# Poactuator_Connectors.net
KiCad netlist of a schematic drawn in Altium Designer
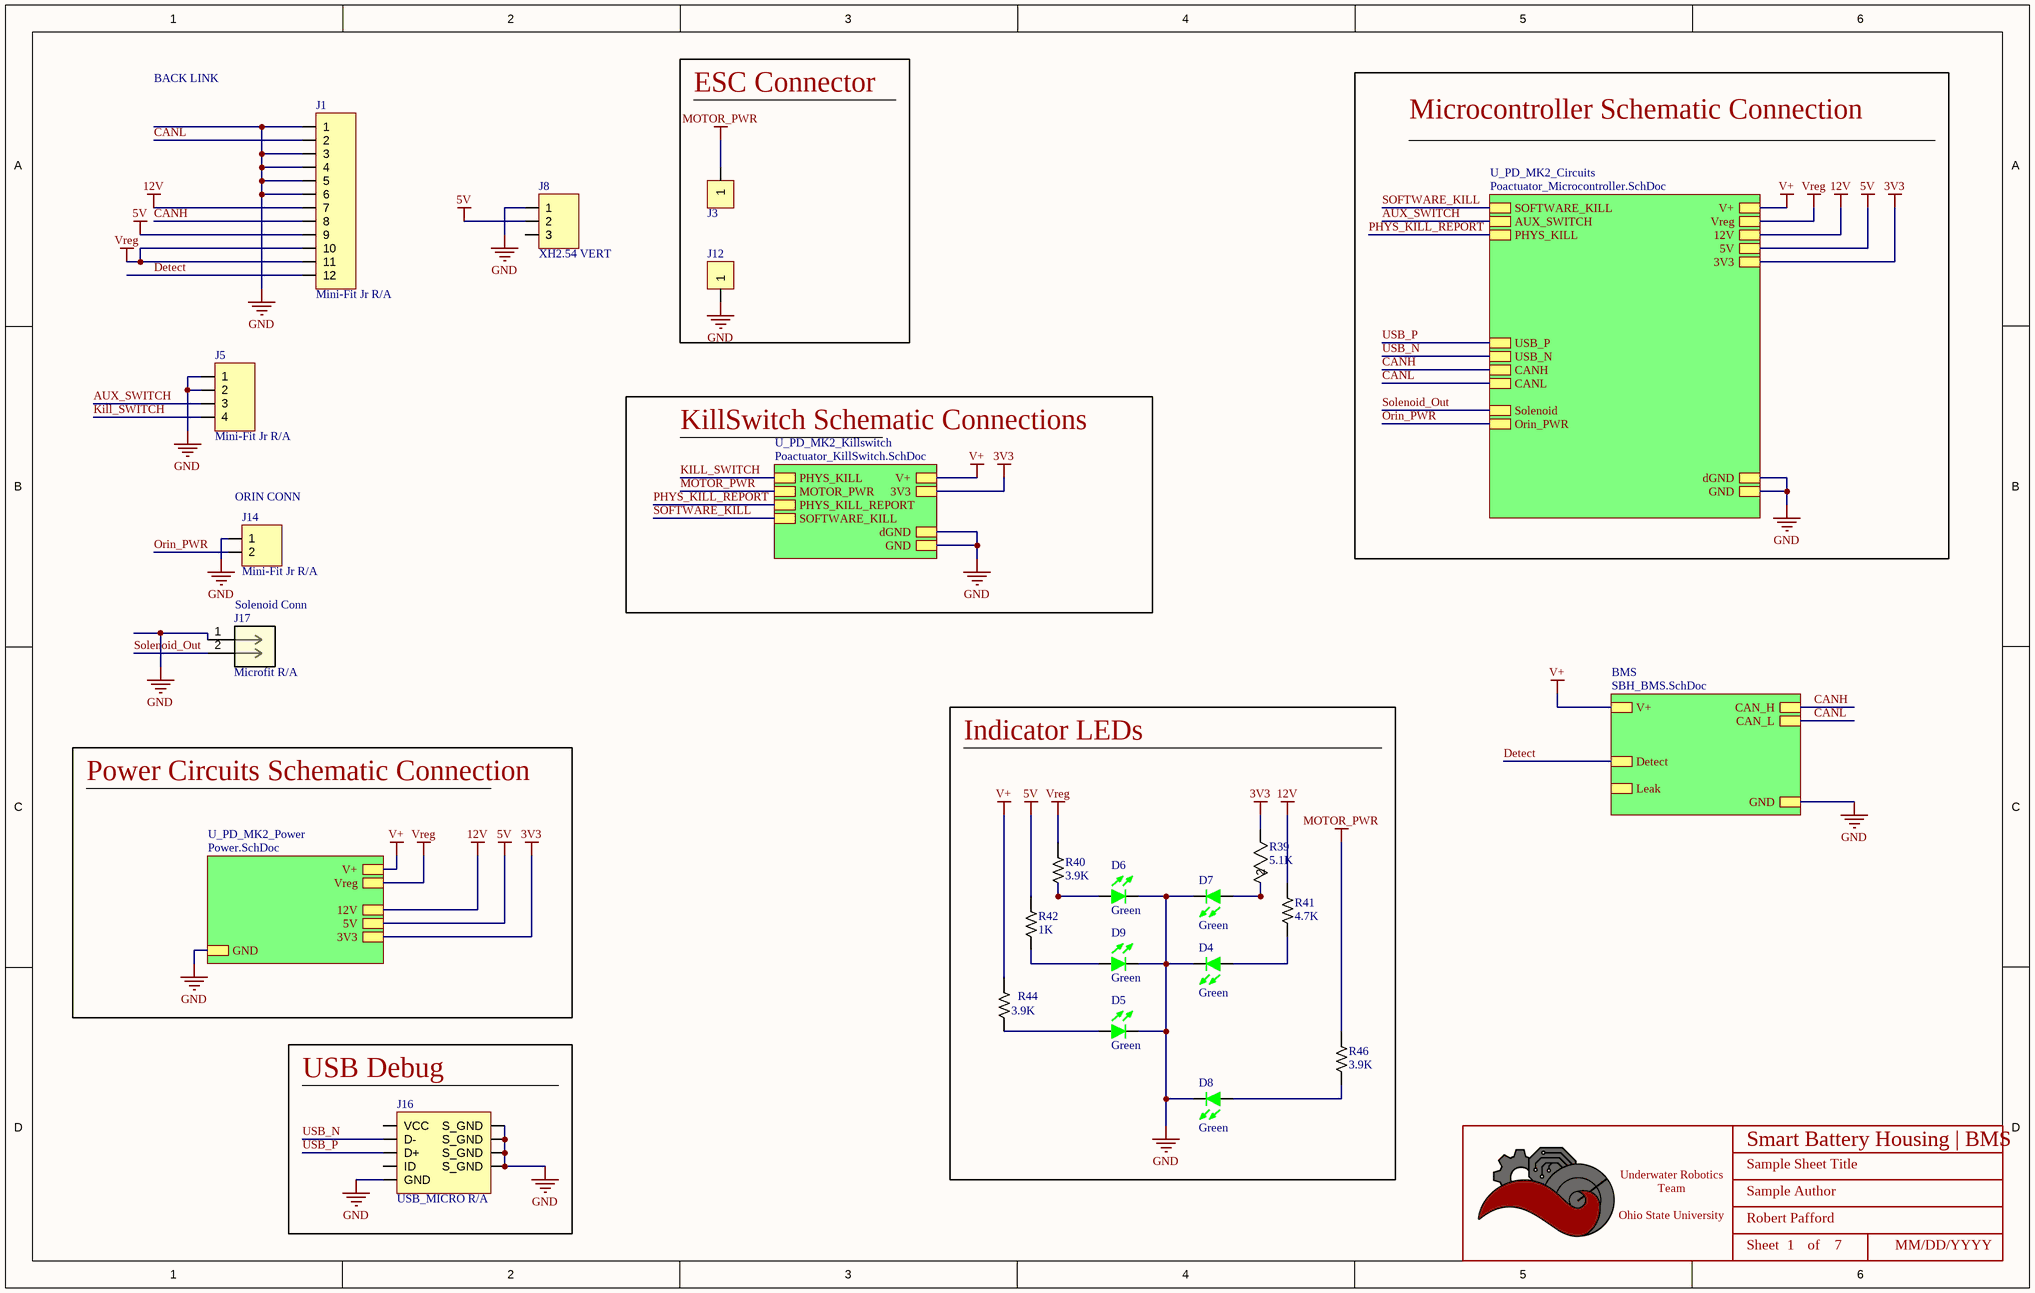
[diagram p0: Poactuator_Connectors.SchDoc]

(export (version "E")
  (design (tool "Eeschema 10.0.6"))
  (components
    (comp (ref "D4")
      (value "IN-S63AT5G")
      (footprint "LED_0603")
      (description "LED Green Vf= 3V If = 0.005A\r\nIN-S63AT5G")
      (fields (field (name "COLOR") "Green") (field (name "MADE BY") "Robert Pafford"))
      (libsource (lib "Diodes") (part "LED_Green_0603_3V"))
    )
    (comp (ref "D5")
      (value "IN-S63AT5G")
      (footprint "LED_0603")
      (description "LED Green Vf= 3V If = 0.005A\r\nIN-S63AT5G")
      (fields (field (name "COLOR") "Green") (field (name "MADE BY") "Robert Pafford"))
      (libsource (lib "Diodes") (part "LED_Green_0603_3V"))
    )
    (comp (ref "D6")
      (value "IN-S63AT5G")
      (footprint "LED_0603")
      (description "LED Green Vf= 3V If = 0.005A\r\nIN-S63AT5G")
      (fields (field (name "COLOR") "Green") (field (name "MADE BY") "Robert Pafford"))
      (libsource (lib "Diodes") (part "LED_Green_0603_3V"))
    )
    (comp (ref "D7")
      (value "IN-S63AT5G")
      (footprint "LED_0603")
      (description "LED Green Vf= 3V If = 0.005A\r\nIN-S63AT5G")
      (fields (field (name "COLOR") "Green") (field (name "MADE BY") "Robert Pafford"))
      (libsource (lib "Diodes") (part "LED_Green_0603_3V"))
    )
    (comp (ref "D8")
      (value "IN-S63AT5G")
      (footprint "LED_0603")
      (description "LED Green Vf= 3V If = 0.005A\r\nIN-S63AT5G")
      (fields (field (name "COLOR") "Green") (field (name "MADE BY") "Robert Pafford"))
      (libsource (lib "Diodes") (part "LED_Green_0603_3V"))
    )
    (comp (ref "D9")
      (value "IN-S63AT5G")
      (footprint "LED_0603")
      (description "LED Green Vf= 3V If = 0.005A\r\nIN-S63AT5G")
      (fields (field (name "COLOR") "Green") (field (name "MADE BY") "Robert Pafford"))
      (libsource (lib "Diodes") (part "LED_Green_0603_3V"))
    )
    (comp (ref "J1")
      (value "Mini-Fit Jr R/A")
      (footprint "CONN_MOLEX_MINIFIT JR_12 POS_R/A")
      (description "Molex Minifit Jr. 5569 \r\n12 Pos R/A Natural")
      (fields (field (name "MANUFACTURER") "Molex") (field (name "CREATED BY") "Flip B"))
      (libsource (lib "Connectors") (part "CONN_MOLEX_MINIFIT JR_12POS_R/A"))
    )
    (comp (ref "J3")
      (value "Redcube M4 Term 85A")
      (footprint "Redcube M4 Term 85A")
      (fields (field (name "CREATED BY") "Nahtan Ayer"))
      (libsource (lib "") (part "Redcube M4 Term 85A_1"))
    )
    (comp (ref "J5")
      (value "Mini-Fit Jr R/A")
      (footprint "CONN_MOLEX_MINIFIT JR_4 POS_R/A")
      (description "Molex Minifit Jr. 5569 \r\n4 Pos R/A Natural")
      (fields (field (name "MANUFACTURER") "Molex") (field (name "CREATED BY") "Flip B"))
      (libsource (lib "Connectors") (part "CONN_MOLEX_MINIFIT JR_4POS_R/A"))
    )
    (comp (ref "J8")
      (value "XH2.54 VERT")
      (footprint "CONN_JST_XH254_3POS_VERT")
      (description "JST XH 2.54mm Pitch 3 Pos Vertical")
      (fields (field (name "MANUFACTURER") "JST") (field (name "CREATED BY") "Robert P"))
      (libsource (lib "Connectors") (part "CONN_JST_XH254_3POS_VERT"))
    )
    (comp (ref "J12")
      (value "Redcube M4 Term 85A")
      (footprint "Redcube M4 Term 85A")
      (fields (field (name "CREATED BY") "Nahtan Ayer"))
      (libsource (lib "Connectors") (part "Redcube M4 Term 85A"))
    )
    (comp (ref "J14")
      (value "Mini-Fit Jr R/A")
      (footprint "CONN_MOLEX_MINIFIT JR_2 POS_R/A")
      (description "Molex Minifit Jr. 5569 \r\n2 Pos R/A Natural")
      (fields (field (name "MANUFACTURER") "Molex") (field (name "CREATED BY") "Robert P"))
      (libsource (lib "Connectors") (part "CONN_MOLEX_MINIFIT JR_2POS_R/A"))
    )
    (comp (ref "J16")
      (value "USB_MICRO R/A")
      (footprint "CONN_MINIUSB")
      (description "Amphenol Micro USB-B\r\nUSB2.0 5 Pin Right Angle SMD")
      (fields (field (name "MANUFACTURER") "Amphenol") (field (name "CREATED BY") "Flip B"))
      (libsource (lib "Connectors") (part "CONN_MICROUSB"))
    )
    (comp (ref "J17")
      (value "Microfit R/A")
      (footprint "CONN_MOLEX_MICROFIT_2 POS_R/A")
      (description "CONN HEADER R/A 2POS")
      (fields (field (name "MANUFACTURER") "Molex"))
      (libsource (lib "Connectors") (part "CONN_MOLEX_MICROFIT_2 POS_R/A"))
    )
    (comp (ref "R39")
      (value "5.1K")
      (footprint "RESISTOR_0603")
      (description "5.1 kOhms ±0.1% 0.1W, 1/10W Chip Resistor 0603 (1608 Metric) Automotive AEC-Q200 Thin Film")
      (fields
        (field (name "MANUFACTURER_PART_NUMBER") "ERA-3AEB512V")
        (field (name "COPYRIGHT") "Copyright (C) 2023 Ultra Librarian. All rights reserved.")
      )
      (libsource (lib "Resistors") (part "ERA-3AEB512V_2"))
    )
    (comp (ref "R40")
      (value "3.9k Ohm 5% 1/10W")
      (footprint "RESISTOR_0603")
      (description "RES 3.9k OHM 1% 1/10W 0603")
      (fields
        (field (name "TOLERANCE") "+/- 1%")
        (field (name "VALUE  (OHMS)") "3.9K")
        (field (name "MADE BY") "Robert Pafford")
      )
      (libsource (lib "Resistors") (part "RESISTOR_3.9K_0603"))
    )
    (comp (ref "R41")
      (value "4.7k Ohm 5% 1/10W")
      (footprint "RESISTOR_0603")
      (description "RES 4.7k OHM 5% 1/10W 0603")
      (fields
        (field (name "TOLERANCE") "+/- 5%")
        (field (name "VALUE  (OHMS)") "4.7K")
        (field (name "MADE BY") "Robert Pafford")
      )
      (libsource (lib "Resistors") (part "RESISTOR_4.7K_0603"))
    )
    (comp (ref "R42")
      (value "1k Ohm 5% 1/8W")
      (footprint "RESISTOR_0603")
      (description "RES 1k OHM 5% 1/8W 0603")
      (fields
        (field (name "TOLERANCE") "+/- 5%")
        (field (name "VALUE  (OHMS)") "1K")
        (field (name "MADE BY") "Robert Pafford")
      )
      (libsource (lib "Resistors") (part "RESISTOR_1K_0603"))
    )
    (comp (ref "R44")
      (value "3.9k Ohm 5% 1/10W")
      (footprint "RESISTOR_0603")
      (description "RES 3.9k OHM 1% 1/10W 0603")
      (fields
        (field (name "TOLERANCE") "+/- 1%")
        (field (name "VALUE  (OHMS)") "3.9K")
        (field (name "MADE BY") "Robert Pafford")
      )
      (libsource (lib "Resistors") (part "RESISTOR_3.9K_0603"))
    )
    (comp (ref "R46")
      (value "3.9k Ohm 5% 1/10W")
      (footprint "RESISTOR_0603")
      (description "RES 3.9k OHM 1% 1/10W 0603")
      (fields
        (field (name "TOLERANCE") "+/- 1%")
        (field (name "VALUE  (OHMS)") "3.9K")
        (field (name "MADE BY") "Robert Pafford")
      )
      (libsource (lib "Resistors") (part "RESISTOR_3.9K_0603"))
    )
  )
  (nets
    (net (code "1") (name "/AUX_SWITCH") (class "Default")
      (node (ref "J5") (pin "3") (pinfunction "3_3") (pintype "passive"))
    )
    (net (code "2") (name "/CANH") (class "Default")
      (node (ref "J1") (pin "8") (pinfunction "8_8") (pintype "passive"))
    )
    (net (code "3") (name "/CANL") (class "Default")
      (node (ref "J1") (pin "2") (pinfunction "2_2") (pintype "passive"))
    )
    (net (code "4") (name "/Detect") (class "Default")
      (node (ref "J1") (pin "12") (pinfunction "12_12") (pintype "passive"))
    )
    (net (code "6") (name "/Kill_SWITCH") (class "Default")
      (node (ref "J5") (pin "4") (pinfunction "4_4") (pintype "passive"))
    )
    (net (code "8") (name "/Orin_PWR") (class "Default")
      (node (ref "J14") (pin "2") (pinfunction "2_2") (pintype "passive"))
    )
    (net (code "11") (name "/Solenoid_Out") (class "Default")
      (node (ref "J17") (pin "2") (pinfunction "2_2") (pintype "passive"))
    )
    (net (code "12") (name "/USB_N") (class "Default")
      (node (ref "J16") (pin "2") (pinfunction "D-_2") (pintype "passive"))
    )
    (net (code "13") (name "/USB_P") (class "Default")
      (node (ref "J16") (pin "3") (pinfunction "D+_3") (pintype "passive"))
    )
    (net (code "14") (name "3V3") (class "Default")
      (node (ref "R39") (pin "1") (pinfunction "1_1") (pintype "passive"))
    )
    (net (code "15") (name "5V") (class "Default")
      (node (ref "J1") (pin "9") (pinfunction "9_9") (pintype "passive"))
      (node (ref "J8") (pin "2") (pinfunction "2_2") (pintype "passive"))
      (node (ref "R42") (pin "1") (pinfunction "1_1") (pintype "passive"))
    )
    (net (code "16") (name "12V") (class "Default")
      (node (ref "J1") (pin "7") (pinfunction "7_7") (pintype "passive"))
      (node (ref "R41") (pin "1") (pinfunction "1_1") (pintype "passive"))
    )
    (net (code "17") (name "GND") (class "Default")
      (node (ref "D4") (pin "2") (pinfunction "2_2") (pintype "passive"))
      (node (ref "D5") (pin "2") (pinfunction "2_2") (pintype "passive"))
      (node (ref "D6") (pin "2") (pinfunction "2_2") (pintype "passive"))
      (node (ref "D7") (pin "2") (pinfunction "2_2") (pintype "passive"))
      (node (ref "D8") (pin "2") (pinfunction "2_2") (pintype "passive"))
      (node (ref "D9") (pin "2") (pinfunction "2_2") (pintype "passive"))
      (node (ref "J1") (pin "1") (pinfunction "1_1") (pintype "passive"))
      (node (ref "J1") (pin "3") (pinfunction "3_3") (pintype "passive"))
      (node (ref "J1") (pin "4") (pinfunction "4_4") (pintype "passive"))
      (node (ref "J1") (pin "5") (pinfunction "5_5") (pintype "passive"))
      (node (ref "J1") (pin "6") (pinfunction "6_6") (pintype "passive"))
      (node (ref "J12") (pin "1") (pinfunction "1_1") (pintype "passive"))
      (node (ref "J14") (pin "1") (pinfunction "1_1") (pintype "passive"))
      (node (ref "J16") (pin "5") (pinfunction "GND_5") (pintype "passive"))
      (node (ref "J16") (pin "6") (pinfunction "S_GND_6") (pintype "passive"))
      (node (ref "J16") (pin "7") (pinfunction "S_GND_7") (pintype "passive"))
      (node (ref "J16") (pin "8") (pinfunction "S_GND_8") (pintype "passive"))
      (node (ref "J16") (pin "9") (pinfunction "S_GND_9") (pintype "passive"))
      (node (ref "J17") (pin "1") (pinfunction "1_1") (pintype "passive"))
      (node (ref "J5") (pin "1") (pinfunction "1_1") (pintype "passive"))
      (node (ref "J5") (pin "2") (pinfunction "2_2") (pintype "passive"))
      (node (ref "J8") (pin "1") (pinfunction "1_1") (pintype "passive"))
    )
    (net (code "18") (name "MOTOR_PWR") (class "Default")
      (node (ref "J3") (pin "1") (pinfunction "1_1") (pintype "passive"))
      (node (ref "R46") (pin "1") (pinfunction "1_1") (pintype "passive"))
    )
    (net (code "19") (name "Net-(D4-Pad1)") (class "Default")
      (node (ref "D4") (pin "1") (pinfunction "1_1") (pintype "passive"))
      (node (ref "R41") (pin "2") (pinfunction "2_2") (pintype "passive"))
    )
    (net (code "20") (name "Net-(D5-Pad1)") (class "Default")
      (node (ref "D5") (pin "1") (pinfunction "1_1") (pintype "passive"))
      (node (ref "R44") (pin "2") (pinfunction "2_2") (pintype "passive"))
    )
    (net (code "21") (name "Net-(D6-Pad1)") (class "Default")
      (node (ref "D6") (pin "1") (pinfunction "1_1") (pintype "passive"))
      (node (ref "R40") (pin "2") (pinfunction "2_2") (pintype "passive"))
    )
    (net (code "22") (name "Net-(D7-Pad1)") (class "Default")
      (node (ref "D7") (pin "1") (pinfunction "1_1") (pintype "passive"))
      (node (ref "R39") (pin "2") (pinfunction "2_2") (pintype "passive"))
    )
    (net (code "23") (name "Net-(D8-Pad1)") (class "Default")
      (node (ref "D8") (pin "1") (pinfunction "1_1") (pintype "passive"))
      (node (ref "R46") (pin "2") (pinfunction "2_2") (pintype "passive"))
    )
    (net (code "24") (name "Net-(D9-Pad1)") (class "Default")
      (node (ref "D9") (pin "1") (pinfunction "1_1") (pintype "passive"))
      (node (ref "R42") (pin "2") (pinfunction "2_2") (pintype "passive"))
    )
    (net (code "25") (name "V+") (class "Default")
      (node (ref "R44") (pin "1") (pinfunction "1_1") (pintype "passive"))
    )
    (net (code "26") (name "Vreg") (class "Default")
      (node (ref "J1") (pin "10") (pinfunction "10_10") (pintype "passive"))
      (node (ref "J1") (pin "11") (pinfunction "11_11") (pintype "passive"))
      (node (ref "R40") (pin "1") (pinfunction "1_1") (pintype "passive"))
    )
    (net (code "27") (name "unconnected-(J8-Pad3)") (class "Default")
      (node (ref "J8") (pin "3") (pinfunction "3_3") (pintype "passive"))
    )
    (net (code "28") (name "unconnected-(J16-ID-Pad4)") (class "Default")
      (node (ref "J16") (pin "4") (pinfunction "ID_4") (pintype "passive"))
    )
    (net (code "29") (name "unconnected-(J16-VCC-Pad1)") (class "Default")
      (node (ref "J16") (pin "1") (pinfunction "VCC_1") (pintype "passive"))
    )
  )
)
